# DCF77-Uhr-V4_1Big_OHW7.net
KiCad netlist of a schematic drawn in EAGLE
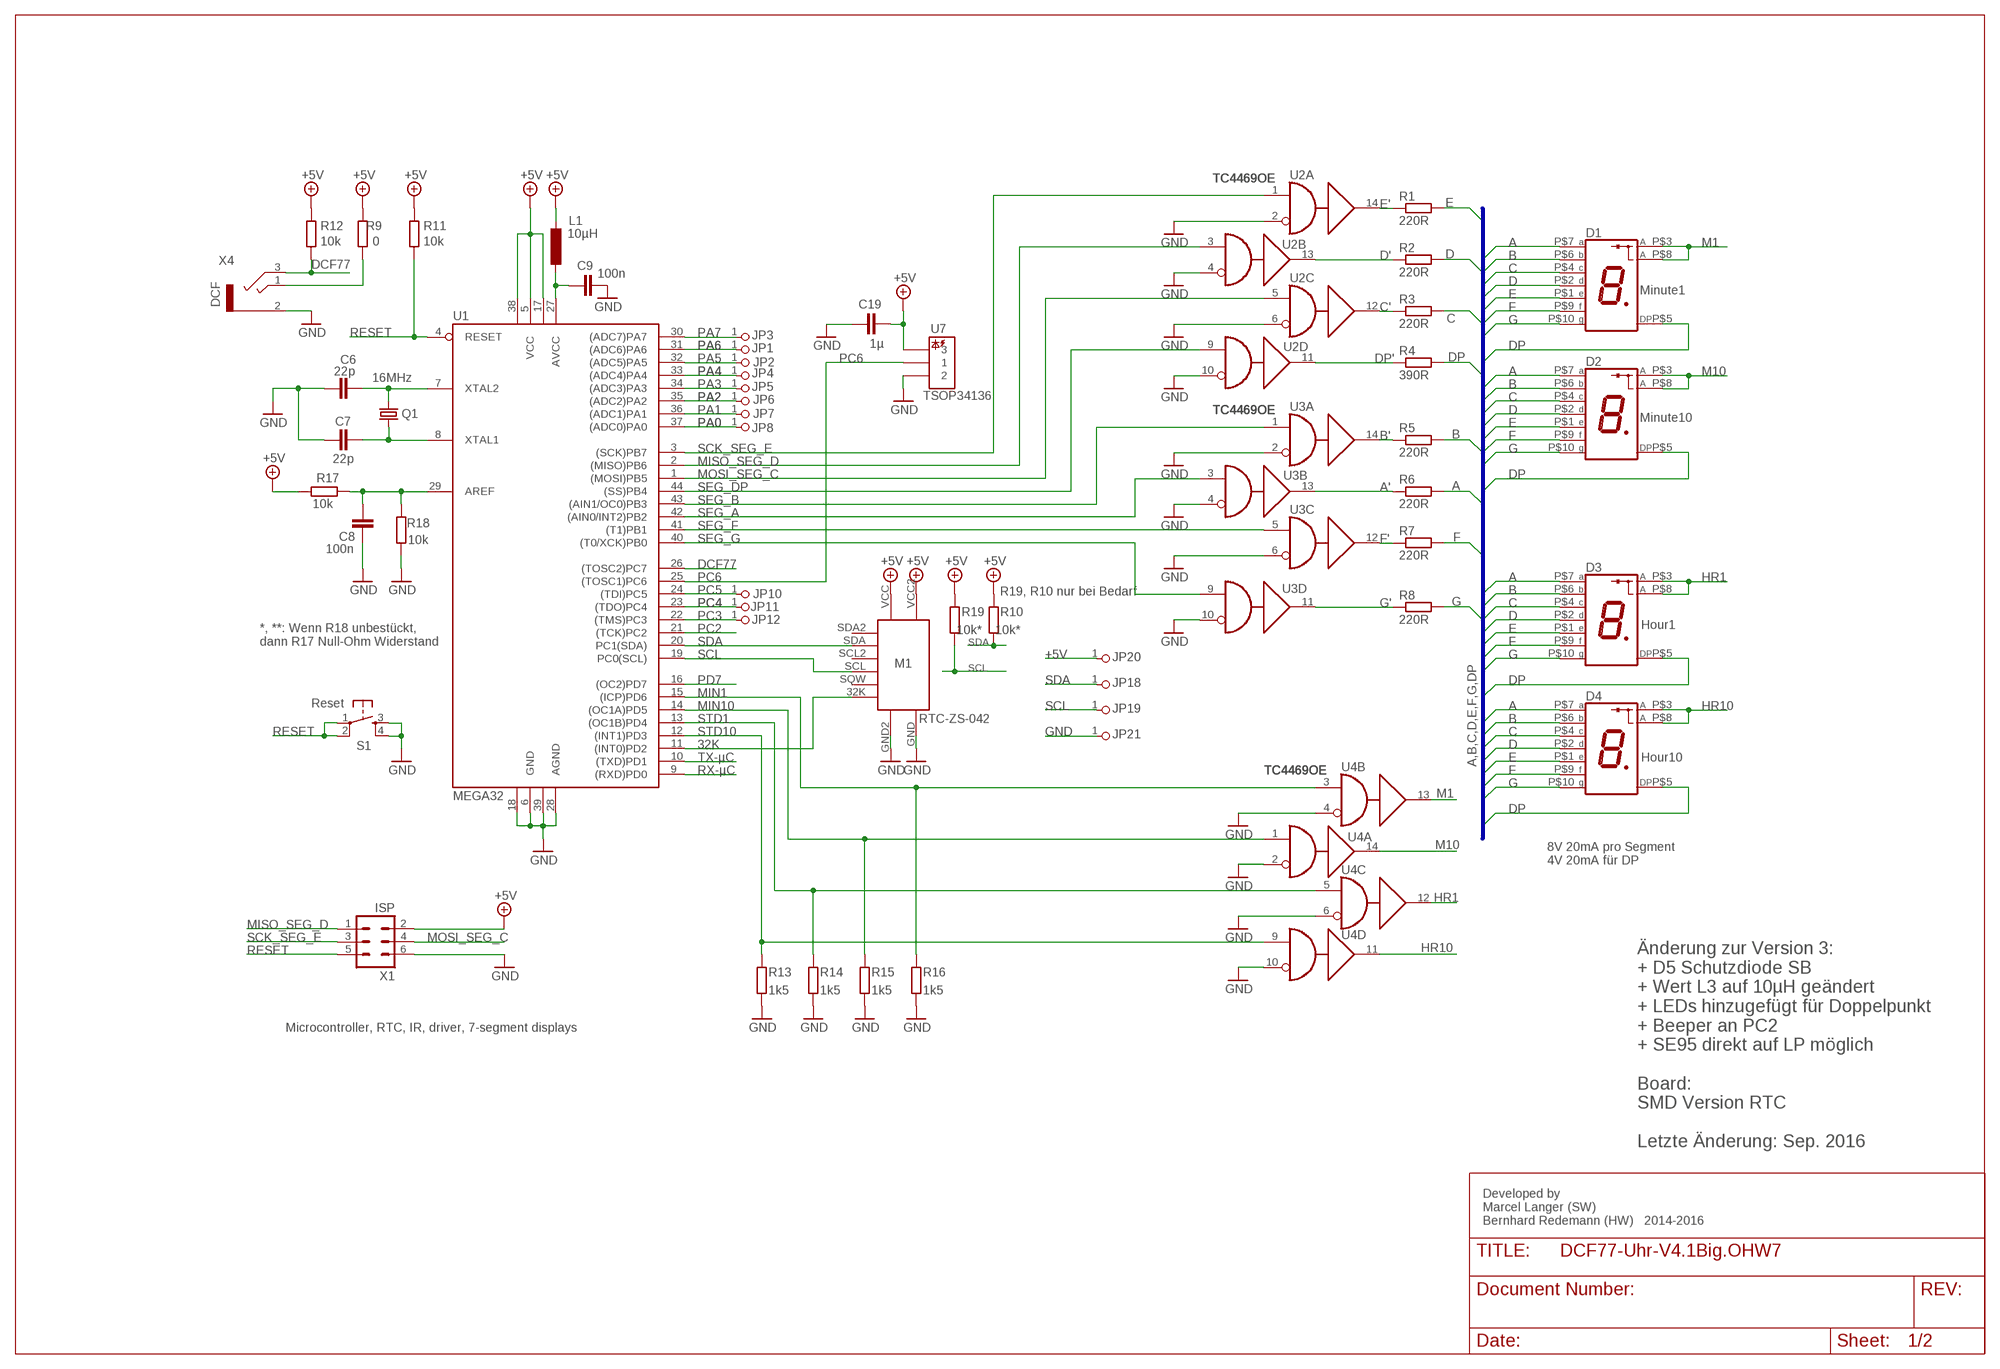
[diagram p0: schematic, sheet 1]
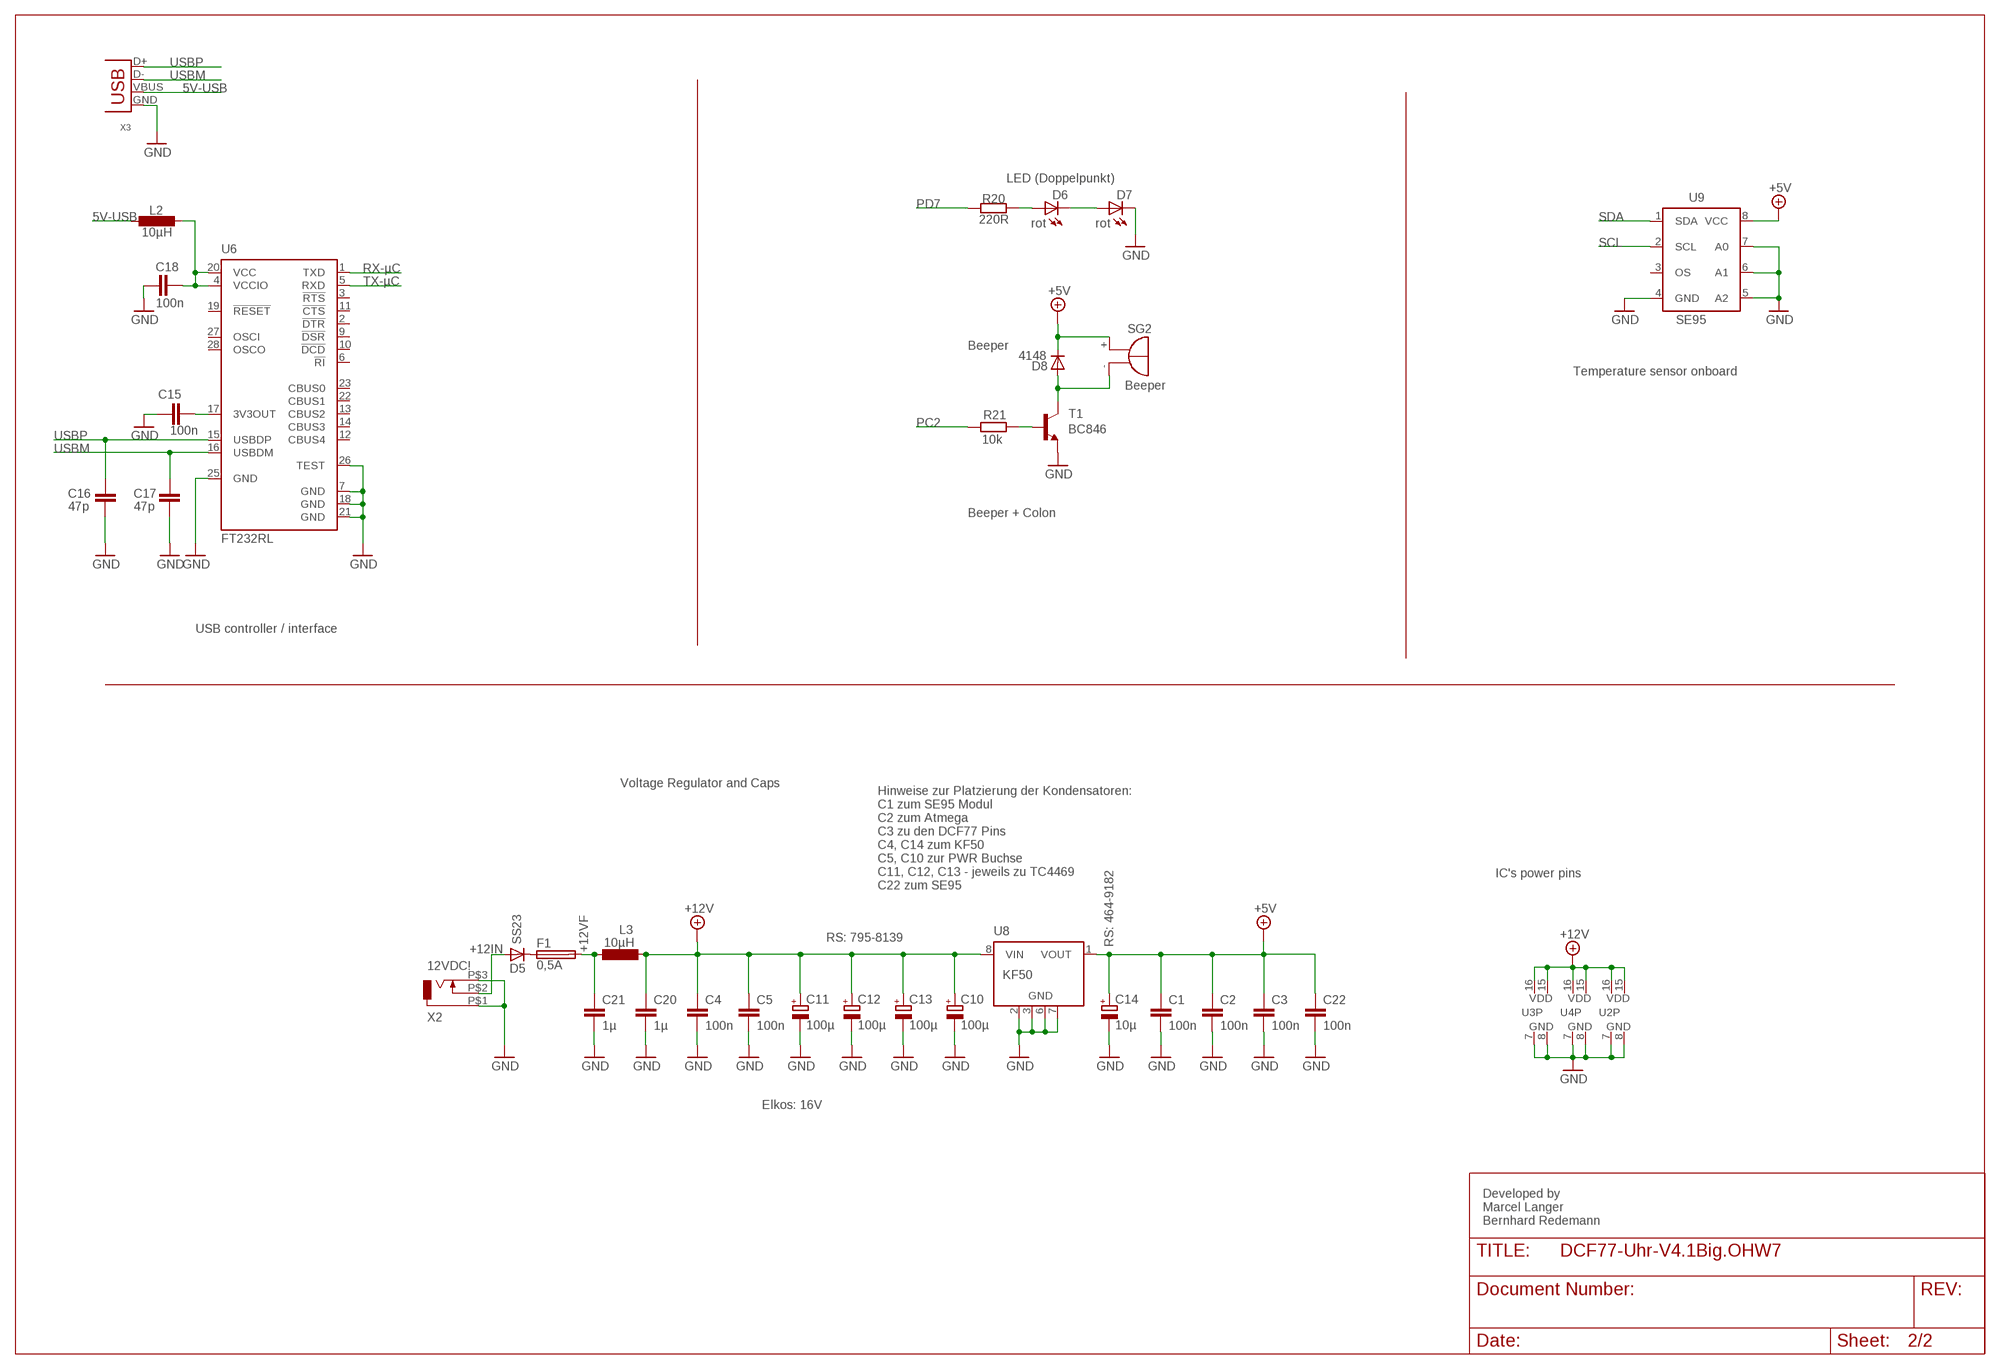
[diagram p1: schematic, sheet 2]

(export (version "E")
  (design (tool "Eeschema 10.0.6"))
  (components
    (comp (ref "C6")
      (value "22p")
      (footprint "eagle-import:C0805")
      (libsource (lib "eagle-import") (part "C-EUC0805"))
    )
    (comp (ref "C7")
      (value "22p")
      (footprint "eagle-import:C0805")
      (libsource (lib "eagle-import") (part "C-EUC0805"))
    )
    (comp (ref "C8")
      (value "100n")
      (footprint "eagle-import:C0805")
      (libsource (lib "eagle-import") (part "C-EUC0805"))
    )
    (comp (ref "C9")
      (value "100n")
      (footprint "eagle-import:C0805")
      (libsource (lib "eagle-import") (part "C-EUC0805"))
    )
    (comp (ref "C19")
      (value "1µ")
      (footprint "eagle-import:C0805")
      (libsource (lib "eagle-import") (part "C-EUC0805"))
    )
    (comp (ref "D1")
      (value "Minute1")
      (footprint "eagle-import:SA40-19EWA")
      (libsource (lib "eagle-import") (part "SA40-19EWA"))
    )
    (comp (ref "D2")
      (value "Minute10")
      (footprint "eagle-import:SA40-19EWA")
      (libsource (lib "eagle-import") (part "SA40-19EWA"))
    )
    (comp (ref "D3")
      (value "Hour1")
      (footprint "eagle-import:SA40-19EWA")
      (libsource (lib "eagle-import") (part "SA40-19EWA"))
    )
    (comp (ref "D4")
      (value "Hour10")
      (footprint "eagle-import:SA40-19EWA")
      (libsource (lib "eagle-import") (part "SA40-19EWA"))
    )
    (comp (ref "JP1")
      (value "PA6")
      (footprint "eagle-import:1X01")
      (libsource (lib "eagle-import") (part "PINHD-1X1"))
    )
    (comp (ref "JP2")
      (value "PC5")
      (footprint "eagle-import:1X01")
      (libsource (lib "eagle-import") (part "PINHD-1X1"))
    )
    (comp (ref "JP3")
      (value "PA6")
      (footprint "eagle-import:1X01")
      (libsource (lib "eagle-import") (part "PINHD-1X1"))
    )
    (comp (ref "JP4")
      (value "PA4")
      (footprint "eagle-import:1X01")
      (libsource (lib "eagle-import") (part "PINHD-1X1"))
    )
    (comp (ref "JP5")
      (value "PA3")
      (footprint "eagle-import:1X01")
      (libsource (lib "eagle-import") (part "PINHD-1X1"))
    )
    (comp (ref "JP6")
      (value "PA2")
      (footprint "eagle-import:1X01")
      (libsource (lib "eagle-import") (part "PINHD-1X1"))
    )
    (comp (ref "JP7")
      (value "PA1")
      (footprint "eagle-import:1X01")
      (libsource (lib "eagle-import") (part "PINHD-1X1"))
    )
    (comp (ref "JP8")
      (value "PA0")
      (footprint "eagle-import:1X01")
      (libsource (lib "eagle-import") (part "PINHD-1X1"))
    )
    (comp (ref "JP10")
      (value "PC5")
      (footprint "eagle-import:1X01")
      (libsource (lib "eagle-import") (part "PINHD-1X1"))
    )
    (comp (ref "JP11")
      (value "PC4")
      (footprint "eagle-import:1X01")
      (libsource (lib "eagle-import") (part "PINHD-1X1"))
    )
    (comp (ref "JP12")
      (value "PC3")
      (footprint "eagle-import:1X01")
      (libsource (lib "eagle-import") (part "PINHD-1X1"))
    )
    (comp (ref "JP18")
      (value "SDA")
      (footprint "eagle-import:1X01")
      (libsource (lib "eagle-import") (part "PINHD-1X1"))
    )
    (comp (ref "JP19")
      (value "SCL")
      (footprint "eagle-import:1X01")
      (libsource (lib "eagle-import") (part "PINHD-1X1"))
    )
    (comp (ref "JP20")
      (value "+5V")
      (footprint "eagle-import:1X01")
      (libsource (lib "eagle-import") (part "PINHD-1X1"))
    )
    (comp (ref "JP21")
      (value "GND")
      (footprint "eagle-import:1X01")
      (libsource (lib "eagle-import") (part "PINHD-1X1"))
    )
    (comp (ref "L1")
      (value "10µH")
      (footprint "eagle-import:L2825P")
      (libsource (lib "eagle-import") (part "L-EUL2825P"))
    )
    (comp (ref "M1")
      (value "RTC-ZS-042")
      (footprint "eagle-import:ZS-042-SMD")
      (libsource (lib "eagle-import") (part "RTC-ZS-042SMD"))
    )
    (comp (ref "Q1")
      (value "16MHz")
      (footprint "eagle-import:HC49UP")
      (libsource (lib "eagle-import") (part "CRYSTALHC49UP"))
    )
    (comp (ref "R1")
      (value "220R")
      (footprint "eagle-import:M0805")
      (libsource (lib "eagle-import") (part "R-EU_M0805"))
    )
    (comp (ref "R2")
      (value "220R")
      (footprint "eagle-import:M0805")
      (libsource (lib "eagle-import") (part "R-EU_M0805"))
    )
    (comp (ref "R3")
      (value "220R")
      (footprint "eagle-import:M0805")
      (libsource (lib "eagle-import") (part "R-EU_M0805"))
    )
    (comp (ref "R4")
      (value "390R")
      (footprint "eagle-import:M0805")
      (libsource (lib "eagle-import") (part "R-EU_M0805"))
    )
    (comp (ref "R5")
      (value "220R")
      (footprint "eagle-import:M0805")
      (libsource (lib "eagle-import") (part "R-EU_M0805"))
    )
    (comp (ref "R6")
      (value "220R")
      (footprint "eagle-import:M0805")
      (libsource (lib "eagle-import") (part "R-EU_M0805"))
    )
    (comp (ref "R7")
      (value "220R")
      (footprint "eagle-import:M0805")
      (libsource (lib "eagle-import") (part "R-EU_M0805"))
    )
    (comp (ref "R8")
      (value "220R")
      (footprint "eagle-import:M0805")
      (libsource (lib "eagle-import") (part "R-EU_M0805"))
    )
    (comp (ref "R9")
      (value "0")
      (footprint "eagle-import:M0805")
      (libsource (lib "eagle-import") (part "R-EU_M0805"))
    )
    (comp (ref "R10")
      (value "10k*")
      (footprint "eagle-import:M0805")
      (libsource (lib "eagle-import") (part "R-EU_M0805"))
    )
    (comp (ref "R11")
      (value "10k")
      (footprint "eagle-import:M0805")
      (libsource (lib "eagle-import") (part "R-EU_M0805"))
    )
    (comp (ref "R12")
      (value "10k")
      (footprint "eagle-import:M0805")
      (libsource (lib "eagle-import") (part "R-EU_M0805"))
    )
    (comp (ref "R13")
      (value "1k5")
      (footprint "eagle-import:M0805")
      (libsource (lib "eagle-import") (part "R-EU_M0805"))
    )
    (comp (ref "R14")
      (value "1k5")
      (footprint "eagle-import:M0805")
      (libsource (lib "eagle-import") (part "R-EU_M0805"))
    )
    (comp (ref "R15")
      (value "1k5")
      (footprint "eagle-import:M0805")
      (libsource (lib "eagle-import") (part "R-EU_M0805"))
    )
    (comp (ref "R16")
      (value "1k5")
      (footprint "eagle-import:M0805")
      (libsource (lib "eagle-import") (part "R-EU_M0805"))
    )
    (comp (ref "R17")
      (value "10k")
      (footprint "eagle-import:M0805")
      (libsource (lib "eagle-import") (part "R-EU_M0805"))
    )
    (comp (ref "R18")
      (value "10k")
      (footprint "eagle-import:M0805")
      (libsource (lib "eagle-import") (part "R-EU_M0805"))
    )
    (comp (ref "R19")
      (value "10k*")
      (footprint "eagle-import:M0805")
      (libsource (lib "eagle-import") (part "R-EU_M0805"))
    )
    (comp (ref "S1")
      (value "Reset")
      (footprint "eagle-import:DTSM-6")
      (libsource (lib "eagle-import") (part "DTSM-6"))
    )
    (comp (ref "U1")
      (value "MEGA32")
      (footprint "eagle-import:TQFP44")
      (libsource (lib "eagle-import") (part "MEGA32-A"))
    )
    (comp (ref "U2")
      (value "TC4469OE")
      (footprint "eagle-import:SO-16DW")
      (fields (field (name "MF") "MICROCHIP") (field (name "MPN") "TC4469COE"))
      (libsource (lib "eagle-import") (part "TC4469OE"))
    )
    (comp (ref "U3")
      (value "TC4469OE")
      (footprint "eagle-import:SO-16DW")
      (fields (field (name "MF") "MICROCHIP") (field (name "MPN") "TC4469COE"))
      (libsource (lib "eagle-import") (part "TC4469OE"))
    )
    (comp (ref "U4")
      (value "TC4469OE")
      (footprint "eagle-import:SO-16DW")
      (fields (field (name "MF") "MICROCHIP") (field (name "MPN") "TC4469COE"))
      (libsource (lib "eagle-import") (part "TC4469OE"))
    )
    (comp (ref "U7")
      (value "TSOP34136")
      (footprint "eagle-import:TSOP348")
      (libsource (lib "eagle-import") (part "TSOP34136"))
    )
    (comp (ref "X1")
      (value "ISP")
      (footprint "eagle-import:ML6")
      (libsource (lib "eagle-import") (part "ML6"))
    )
    (comp (ref "X4")
      (value "DCF")
      (footprint "eagle-import:1502_01")
      (libsource (lib "eagle-import") (part "1502_01"))
    )
    (comp (ref "C1")
      (value "100n")
      (footprint "eagle-import:C0805")
      (libsource (lib "eagle-import") (part "C-EUC0805"))
    )
    (comp (ref "C2")
      (value "100n")
      (footprint "eagle-import:C0805")
      (libsource (lib "eagle-import") (part "C-EUC0805"))
    )
    (comp (ref "C3")
      (value "100n")
      (footprint "eagle-import:C0805")
      (libsource (lib "eagle-import") (part "C-EUC0805"))
    )
    (comp (ref "C4")
      (value "100n")
      (footprint "eagle-import:C0805")
      (libsource (lib "eagle-import") (part "C-EUC0805"))
    )
    (comp (ref "C5")
      (value "100n")
      (footprint "eagle-import:C0805")
      (libsource (lib "eagle-import") (part "C-EUC0805"))
    )
    (comp (ref "C10")
      (value "100µ")
      (footprint "eagle-import:PANASONIC_D")
      (libsource (lib "eagle-import") (part "CPOL-EUD"))
    )
    (comp (ref "C11")
      (value "100µ")
      (footprint "eagle-import:PANASONIC_D")
      (libsource (lib "eagle-import") (part "CPOL-EUD"))
    )
    (comp (ref "C12")
      (value "100µ")
      (footprint "eagle-import:PANASONIC_D")
      (libsource (lib "eagle-import") (part "CPOL-EUD"))
    )
    (comp (ref "C13")
      (value "100µ")
      (footprint "eagle-import:PANASONIC_D")
      (libsource (lib "eagle-import") (part "CPOL-EUD"))
    )
    (comp (ref "C14")
      (value "10µ")
      (footprint "eagle-import:PANASONIC_B")
      (libsource (lib "eagle-import") (part "CPOL-EUB"))
    )
    (comp (ref "C15")
      (value "100n")
      (footprint "eagle-import:C0805")
      (libsource (lib "eagle-import") (part "C-EUC0805"))
    )
    (comp (ref "C16")
      (value "47p")
      (footprint "eagle-import:C0805")
      (libsource (lib "eagle-import") (part "C-EUC0805"))
    )
    (comp (ref "C17")
      (value "47p")
      (footprint "eagle-import:C0805")
      (libsource (lib "eagle-import") (part "C-EUC0805"))
    )
    (comp (ref "C18")
      (value "100n")
      (footprint "eagle-import:C0805")
      (libsource (lib "eagle-import") (part "C-EUC0805"))
    )
    (comp (ref "C20")
      (value "1µ")
      (footprint "eagle-import:C0805")
      (libsource (lib "eagle-import") (part "C-EUC0805"))
    )
    (comp (ref "C21")
      (value "1µ")
      (footprint "eagle-import:C0805")
      (libsource (lib "eagle-import") (part "C-EUC0805"))
    )
    (comp (ref "C22")
      (value "100n")
      (footprint "eagle-import:C0805")
      (libsource (lib "eagle-import") (part "C-EUC0805"))
    )
    (comp (ref "D5")
      (value "SS23")
      (footprint "eagle-import:SMB")
      (libsource (lib "eagle-import") (part "DIODE-SMB"))
    )
    (comp (ref "D6")
      (value "rot")
      (footprint "eagle-import:LED10MM")
      (libsource (lib "eagle-import") (part "LED10MM"))
    )
    (comp (ref "D7")
      (value "rot")
      (footprint "eagle-import:LED10MM")
      (libsource (lib "eagle-import") (part "LED10MM"))
    )
    (comp (ref "D8")
      (value "4148")
      (footprint "eagle-import:DO214BA")
      (libsource (lib "eagle-import") (part "DIODE-DO214BA"))
    )
    (comp (ref "F1")
      (value "0,5A")
      (footprint "eagle-import:19560")
      (fields (field (name "MPN") "56000001009"))
      (libsource (lib "eagle-import") (part "19560"))
    )
    (comp (ref "L2")
      (value "10µH")
      (footprint "eagle-import:L2825P")
      (libsource (lib "eagle-import") (part "L-EUL2825P"))
    )
    (comp (ref "L3")
      (value "10µH")
      (footprint "eagle-import:L2825P")
      (libsource (lib "eagle-import") (part "L-EUL2825P"))
    )
    (comp (ref "R20")
      (value "220R")
      (footprint "eagle-import:M0805")
      (libsource (lib "eagle-import") (part "R-EU_M0805"))
    )
    (comp (ref "R21")
      (value "10k")
      (footprint "eagle-import:M0805")
      (libsource (lib "eagle-import") (part "R-EU_M0805"))
    )
    (comp (ref "SG2")
      (value "Beeper")
      (footprint "eagle-import:BMT1205XH7.5")
      (libsource (lib "eagle-import") (part "BMT1205XH7.5"))
    )
    (comp (ref "T1")
      (value "BC846")
      (footprint "eagle-import:SOT23")
      (libsource (lib "eagle-import") (part "BC846"))
    )
    (comp (ref "U6")
      (value "FT232RL")
      (footprint "eagle-import:SSOP28")
      (libsource (lib "eagle-import") (part "FT232RL"))
    )
    (comp (ref "U8")
      (value "KF50")
      (footprint "eagle-import:SO08")
      (libsource (lib "eagle-import") (part "78LSMD05"))
    )
    (comp (ref "U9")
      (value "SE95")
      (footprint "eagle-import:SO08")
      (libsource (lib "eagle-import") (part "LM75SMD"))
    )
    (comp (ref "X2")
      (value "12VDC!")
      (footprint "eagle-import:DCJ04-021")
      (libsource (lib "eagle-import") (part "DCJ0202DCJ04-021"))
    )
    (comp (ref "X3")
      (value "USB")
      (footprint "eagle-import:USB-B180")
      (libsource (lib "eagle-import") (part "USB-B180"))
    )
  )
  (nets
    (net (code "1") (name "+5V") (class "Default")
      (node (ref "C1") (pin "1") (pinfunction "1_1") (pintype "passive"))
      (node (ref "C14") (pin "+") (pinfunction "+_+") (pintype "passive"))
      (node (ref "C19") (pin "2") (pinfunction "2_2") (pintype "passive"))
      (node (ref "C2") (pin "1") (pinfunction "1_1") (pintype "passive"))
      (node (ref "C22") (pin "1") (pinfunction "1_1") (pintype "passive"))
      (node (ref "C3") (pin "1") (pinfunction "1_1") (pintype "passive"))
      (node (ref "D8") (pin "C") (pinfunction "C_C") (pintype "passive"))
      (node (ref "JP20") (pin "1") (pinfunction "1_1") (pintype "passive"))
      (node (ref "L1") (pin "2") (pinfunction "2_2") (pintype "passive"))
      (node (ref "M1") (pin "VCC") (pinfunction "P$9_VCC") (pintype "bidirectional"))
      (node (ref "M1") (pin "VCC2") (pinfunction "P$10_VCC2") (pintype "bidirectional"))
      (node (ref "R10") (pin "2") (pinfunction "2_2") (pintype "passive"))
      (node (ref "R11") (pin "2") (pinfunction "2_2") (pintype "passive"))
      (node (ref "R12") (pin "2") (pinfunction "2_2") (pintype "passive"))
      (node (ref "R17") (pin "1") (pinfunction "1_1") (pintype "passive"))
      (node (ref "R19") (pin "2") (pinfunction "2_2") (pintype "passive"))
      (node (ref "R9") (pin "2") (pinfunction "2_2") (pintype "passive"))
      (node (ref "SG2") (pin "+") (pinfunction "+_+") (pintype "passive"))
      (node (ref "U1") (pin "17") (pinfunction "VCC1_17") (pintype "power_in"))
      (node (ref "U1") (pin "38") (pinfunction "VCC2_38") (pintype "power_in"))
      (node (ref "U1") (pin "5") (pinfunction "VCC_5") (pintype "power_in"))
      (node (ref "U7") (pin "3") (pinfunction "3_3") (pintype "power_in"))
      (node (ref "U8") (pin "1") (pinfunction "VOUT_1") (pintype "bidirectional"))
      (node (ref "U9") (pin "8") (pinfunction "VCC_8") (pintype "power_in"))
      (node (ref "X1") (pin "2") (pinfunction "2_2") (pintype "passive"))
    )
    (net (code "2") (name "+12IN") (class "Default")
      (node (ref "D5") (pin "A") (pinfunction "A_A") (pintype "passive"))
      (node (ref "X2") (pin "P$2") (pinfunction "2_P$2") (pintype "passive"))
    )
    (net (code "3") (name "+12V") (class "Default")
      (node (ref "C10") (pin "+") (pinfunction "+_+") (pintype "passive"))
      (node (ref "C11") (pin "+") (pinfunction "+_+") (pintype "passive"))
      (node (ref "C12") (pin "+") (pinfunction "+_+") (pintype "passive"))
      (node (ref "C13") (pin "+") (pinfunction "+_+") (pintype "passive"))
      (node (ref "C20") (pin "1") (pinfunction "1_1") (pintype "passive"))
      (node (ref "C4") (pin "1") (pinfunction "1_1") (pintype "passive"))
      (node (ref "C5") (pin "1") (pinfunction "1_1") (pintype "passive"))
      (node (ref "L3") (pin "1") (pinfunction "1_1") (pintype "passive"))
      (node (ref "U2") (pin "15") (pinfunction "VDD_15") (pintype "power_in"))
      (node (ref "U2") (pin "16") (pinfunction "VDD_16") (pintype "power_in"))
      (node (ref "U3") (pin "15") (pinfunction "VDD_15") (pintype "power_in"))
      (node (ref "U3") (pin "16") (pinfunction "VDD_16") (pintype "power_in"))
      (node (ref "U4") (pin "15") (pinfunction "VDD_15") (pintype "power_in"))
      (node (ref "U4") (pin "16") (pinfunction "VDD_16") (pintype "power_in"))
      (node (ref "U8") (pin "8") (pinfunction "VIN_8") (pintype "passive"))
    )
    (net (code "4") (name "+12VF") (class "Default")
      (node (ref "C21") (pin "1") (pinfunction "1_1") (pintype "passive"))
      (node (ref "F1") (pin "2") (pinfunction "2_2") (pintype "passive"))
      (node (ref "L3") (pin "2") (pinfunction "2_2") (pintype "passive"))
    )
    (net (code "6") (name "5V-USB") (class "Default")
      (node (ref "L2") (pin "2") (pinfunction "2_2") (pintype "passive"))
      (node (ref "X3") (pin "VBUS") (pinfunction "VBUS_VBUS") (pintype "bidirectional"))
    )
    (net (code "7") (name "32K") (class "Default")
      (node (ref "M1") (pin "32K") (pinfunction "P$1_32K") (pintype "bidirectional"))
      (node (ref "U1") (pin "11") (pinfunction "(INT0)PD2_11") (pintype "bidirectional"))
    )
    (net (code "8") (name "A") (class "Default")
      (node (ref "D1") (pin "P$7") (pinfunction "A_P$7") (pintype "passive"))
      (node (ref "D2") (pin "P$7") (pinfunction "A_P$7") (pintype "passive"))
      (node (ref "D3") (pin "P$7") (pinfunction "A_P$7") (pintype "passive"))
      (node (ref "D4") (pin "P$7") (pinfunction "A_P$7") (pintype "passive"))
      (node (ref "R6") (pin "2") (pinfunction "2_2") (pintype "passive"))
    )
    (net (code "9") (name "A'") (class "Default")
      (node (ref "R6") (pin "1") (pinfunction "1_1") (pintype "passive"))
      (node (ref "U3") (pin "13") (pinfunction "Y_13") (pintype "output"))
    )
    (net (code "10") (name "B") (class "Default")
      (node (ref "D1") (pin "P$6") (pinfunction "B_P$6") (pintype "passive"))
      (node (ref "D2") (pin "P$6") (pinfunction "B_P$6") (pintype "passive"))
      (node (ref "D3") (pin "P$6") (pinfunction "B_P$6") (pintype "passive"))
      (node (ref "D4") (pin "P$6") (pinfunction "B_P$6") (pintype "passive"))
      (node (ref "R5") (pin "2") (pinfunction "2_2") (pintype "passive"))
    )
    (net (code "11") (name "B'") (class "Default")
      (node (ref "R5") (pin "1") (pinfunction "1_1") (pintype "passive"))
      (node (ref "U3") (pin "14") (pinfunction "Y_14") (pintype "output"))
    )
    (net (code "12") (name "C") (class "Default")
      (node (ref "D1") (pin "P$4") (pinfunction "C_P$4") (pintype "passive"))
      (node (ref "D2") (pin "P$4") (pinfunction "C_P$4") (pintype "passive"))
      (node (ref "D3") (pin "P$4") (pinfunction "C_P$4") (pintype "passive"))
      (node (ref "D4") (pin "P$4") (pinfunction "C_P$4") (pintype "passive"))
      (node (ref "R3") (pin "2") (pinfunction "2_2") (pintype "passive"))
    )
    (net (code "13") (name "C'") (class "Default")
      (node (ref "R3") (pin "1") (pinfunction "1_1") (pintype "passive"))
      (node (ref "U2") (pin "12") (pinfunction "Y_12") (pintype "output"))
    )
    (net (code "14") (name "D") (class "Default")
      (node (ref "D1") (pin "P$2") (pinfunction "D_P$2") (pintype "passive"))
      (node (ref "D2") (pin "P$2") (pinfunction "D_P$2") (pintype "passive"))
      (node (ref "D3") (pin "P$2") (pinfunction "D_P$2") (pintype "passive"))
      (node (ref "D4") (pin "P$2") (pinfunction "D_P$2") (pintype "passive"))
      (node (ref "R2") (pin "2") (pinfunction "2_2") (pintype "passive"))
    )
    (net (code "15") (name "D'") (class "Default")
      (node (ref "R2") (pin "1") (pinfunction "1_1") (pintype "passive"))
      (node (ref "U2") (pin "13") (pinfunction "Y_13") (pintype "output"))
    )
    (net (code "16") (name "DCF77") (class "Default")
      (node (ref "R12") (pin "1") (pinfunction "1_1") (pintype "passive"))
      (node (ref "U1") (pin "26") (pinfunction "(TOSC2)PC7_26") (pintype "bidirectional"))
      (node (ref "X4") (pin "3") (pinfunction "2_3") (pintype "passive"))
    )
    (net (code "17") (name "DP") (class "Default")
      (node (ref "D1") (pin "P$5") (pinfunction "DP_P$5") (pintype "passive"))
      (node (ref "D2") (pin "P$5") (pinfunction "DP_P$5") (pintype "passive"))
      (node (ref "D3") (pin "P$5") (pinfunction "DP_P$5") (pintype "passive"))
      (node (ref "D4") (pin "P$5") (pinfunction "DP_P$5") (pintype "passive"))
      (node (ref "R4") (pin "2") (pinfunction "2_2") (pintype "passive"))
    )
    (net (code "18") (name "DP'") (class "Default")
      (node (ref "R4") (pin "1") (pinfunction "1_1") (pintype "passive"))
      (node (ref "U2") (pin "11") (pinfunction "Y_11") (pintype "output"))
    )
    (net (code "19") (name "E") (class "Default")
      (node (ref "D1") (pin "P$1") (pinfunction "E_P$1") (pintype "passive"))
      (node (ref "D2") (pin "P$1") (pinfunction "E_P$1") (pintype "passive"))
      (node (ref "D3") (pin "P$1") (pinfunction "E_P$1") (pintype "passive"))
      (node (ref "D4") (pin "P$1") (pinfunction "E_P$1") (pintype "passive"))
      (node (ref "R1") (pin "2") (pinfunction "2_2") (pintype "passive"))
    )
    (net (code "20") (name "E'") (class "Default")
      (node (ref "R1") (pin "1") (pinfunction "1_1") (pintype "passive"))
      (node (ref "U2") (pin "14") (pinfunction "Y_14") (pintype "output"))
    )
    (net (code "21") (name "F") (class "Default")
      (node (ref "D1") (pin "P$9") (pinfunction "F_P$9") (pintype "passive"))
      (node (ref "D2") (pin "P$9") (pinfunction "F_P$9") (pintype "passive"))
      (node (ref "D3") (pin "P$9") (pinfunction "F_P$9") (pintype "passive"))
      (node (ref "D4") (pin "P$9") (pinfunction "F_P$9") (pintype "passive"))
      (node (ref "R7") (pin "2") (pinfunction "2_2") (pintype "passive"))
    )
    (net (code "22") (name "F'") (class "Default")
      (node (ref "R7") (pin "1") (pinfunction "1_1") (pintype "passive"))
      (node (ref "U3") (pin "12") (pinfunction "Y_12") (pintype "output"))
    )
    (net (code "23") (name "G") (class "Default")
      (node (ref "D1") (pin "P$10") (pinfunction "G_P$10") (pintype "passive"))
      (node (ref "D2") (pin "P$10") (pinfunction "G_P$10") (pintype "passive"))
      (node (ref "D3") (pin "P$10") (pinfunction "G_P$10") (pintype "passive"))
      (node (ref "D4") (pin "P$10") (pinfunction "G_P$10") (pintype "passive"))
      (node (ref "R8") (pin "2") (pinfunction "2_2") (pintype "passive"))
    )
    (net (code "24") (name "G'") (class "Default")
      (node (ref "R8") (pin "1") (pinfunction "1_1") (pintype "passive"))
      (node (ref "U3") (pin "11") (pinfunction "Y_11") (pintype "output"))
    )
    (net (code "25") (name "GND") (class "Default")
      (node (ref "C1") (pin "2") (pinfunction "2_2") (pintype "passive"))
      (node (ref "C10") (pin "-") (pinfunction "-_-") (pintype "passive"))
      (node (ref "C11") (pin "-") (pinfunction "-_-") (pintype "passive"))
      (node (ref "C12") (pin "-") (pinfunction "-_-") (pintype "passive"))
      (node (ref "C13") (pin "-") (pinfunction "-_-") (pintype "passive"))
      (node (ref "C14") (pin "-") (pinfunction "-_-") (pintype "passive"))
      (node (ref "C15") (pin "1") (pinfunction "1_1") (pintype "passive"))
      (node (ref "C16") (pin "1") (pinfunction "1_1") (pintype "passive"))
      (node (ref "C17") (pin "1") (pinfunction "1_1") (pintype "passive"))
      (node (ref "C18") (pin "1") (pinfunction "1_1") (pintype "passive"))
      (node (ref "C19") (pin "1") (pinfunction "1_1") (pintype "passive"))
      (node (ref "C2") (pin "2") (pinfunction "2_2") (pintype "passive"))
      (node (ref "C20") (pin "2") (pinfunction "2_2") (pintype "passive"))
      (node (ref "C21") (pin "2") (pinfunction "2_2") (pintype "passive"))
      (node (ref "C22") (pin "2") (pinfunction "2_2") (pintype "passive"))
      (node (ref "C3") (pin "2") (pinfunction "2_2") (pintype "passive"))
      (node (ref "C4") (pin "2") (pinfunction "2_2") (pintype "passive"))
      (node (ref "C5") (pin "2") (pinfunction "2_2") (pintype "passive"))
      (node (ref "C6") (pin "1") (pinfunction "1_1") (pintype "passive"))
      (node (ref "C7") (pin "1") (pinfunction "1_1") (pintype "passive"))
      (node (ref "C8") (pin "1") (pinfunction "1_1") (pintype "passive"))
      (node (ref "C9") (pin "2") (pinfunction "2_2") (pintype "passive"))
      (node (ref "D7") (pin "K") (pinfunction "C_K") (pintype "passive"))
      (node (ref "JP21") (pin "1") (pinfunction "1_1") (pintype "passive"))
      (node (ref "M1") (pin "GND") (pinfunction "P$7_GND") (pintype "bidirectional"))
      (node (ref "M1") (pin "GND2") (pinfunction "P$8_GND2") (pintype "bidirectional"))
      (node (ref "R13") (pin "1") (pinfunction "1_1") (pintype "passive"))
      (node (ref "R14") (pin "1") (pinfunction "1_1") (pintype "passive"))
      (node (ref "R15") (pin "1") (pinfunction "1_1") (pintype "passive"))
      (node (ref "R16") (pin "1") (pinfunction "1_1") (pintype "passive"))
      (node (ref "R18") (pin "1") (pinfunction "1_1") (pintype "passive"))
      (node (ref "S1") (pin "3") (pinfunction "3_3") (pintype "passive"))
      (node (ref "S1") (pin "4") (pinfunction "4_4") (pintype "passive"))
      (node (ref "T1") (pin "2") (pinfunction "E_2") (pintype "passive"))
      (node (ref "U1") (pin "18") (pinfunction "GND1_18") (pintype "power_in"))
      (node (ref "U1") (pin "28") (pinfunction "AGND_28") (pintype "power_in"))
      (node (ref "U1") (pin "39") (pinfunction "GND2_39") (pintype "power_in"))
      (node (ref "U1") (pin "6") (pinfunction "GND_6") (pintype "power_in"))
      (node (ref "U2") (pin "10") (pinfunction "B_10") (pintype "input"))
      (node (ref "U2") (pin "2") (pinfunction "B_2") (pintype "input"))
      (node (ref "U2") (pin "4") (pinfunction "B_4") (pintype "input"))
      (node (ref "U2") (pin "6") (pinfunction "B_6") (pintype "input"))
      (node (ref "U2") (pin "7") (pinfunction "GND_7") (pintype "power_in"))
      (node (ref "U2") (pin "8") (pinfunction "GND_8") (pintype "power_in"))
      (node (ref "U3") (pin "10") (pinfunction "B_10") (pintype "input"))
      (node (ref "U3") (pin "2") (pinfunction "B_2") (pintype "input"))
      (node (ref "U3") (pin "4") (pinfunction "B_4") (pintype "input"))
      (node (ref "U3") (pin "6") (pinfunction "B_6") (pintype "input"))
      (node (ref "U3") (pin "7") (pinfunction "GND_7") (pintype "power_in"))
      (node (ref "U3") (pin "8") (pinfunction "GND_8") (pintype "power_in"))
      (node (ref "U4") (pin "10") (pinfunction "B_10") (pintype "input"))
      (node (ref "U4") (pin "2") (pinfunction "B_2") (pintype "input"))
      (node (ref "U4") (pin "4") (pinfunction "B_4") (pintype "input"))
      (node (ref "U4") (pin "6") (pinfunction "B_6") (pintype "input"))
      (node (ref "U4") (pin "7") (pinfunction "GND_7") (pintype "power_in"))
      (node (ref "U4") (pin "8") (pinfunction "GND_8") (pintype "power_in"))
      (node (ref "U6") (pin "18") (pinfunction "GND_18") (pintype "power_in"))
      (node (ref "U6") (pin "21") (pinfunction "GND_21") (pintype "power_in"))
      (node (ref "U6") (pin "25") (pinfunction "GND_25") (pintype "power_in"))
      (node (ref "U6") (pin "26") (pinfunction "TEST_26") (pintype "input"))
      (node (ref "U6") (pin "7") (pinfunction "GND_7") (pintype "power_in"))
      (node (ref "U7") (pin "2") (pinfunction "2_2") (pintype "bidirectional"))
      (node (ref "U8") (pin "2") (pinfunction "GND_2") (pintype "power_in"))
      (node (ref "U8") (pin "3") (pinfunction "GND_3") (pintype "power_in"))
      (node (ref "U8") (pin "6") (pinfunction "GND_6") (pintype "power_in"))
      (node (ref "U8") (pin "7") (pinfunction "GND_7") (pintype "power_in"))
      (node (ref "U9") (pin "4") (pinfunction "GND_4") (pintype "power_in"))
      (node (ref "U9") (pin "5") (pinfunction "A2_5") (pintype "input"))
      (node (ref "U9") (pin "6") (pinfunction "A1_6") (pintype "input"))
      (node (ref "U9") (pin "7") (pinfunction "A0_7") (pintype "input"))
      (node (ref "X1") (pin "6") (pinfunction "6_6") (pintype "passive"))
      (node (ref "X2") (pin "P$1") (pinfunction "1_P$1") (pintype "passive"))
      (node (ref "X2") (pin "P$3") (pinfunction "3_P$3") (pintype "passive"))
      (node (ref "X3") (pin "GND") (pinfunction "GND_GND") (pintype "bidirectional"))
      (node (ref "X4") (pin "2") (pinfunction "1_2") (pintype "passive"))
    )
    (net (code "26") (name "HR1") (class "Default")
      (node (ref "D3") (pin "P$3") (pinfunction "A_P$3") (pintype "passive"))
      (node (ref "D3") (pin "P$8") (pinfunction "A_P$8") (pintype "passive"))
      (node (ref "U4") (pin "12") (pinfunction "Y_12") (pintype "output"))
    )
    (net (code "27") (name "HR10") (class "Default")
      (node (ref "D4") (pin "P$3") (pinfunction "A_P$3") (pintype "passive"))
      (node (ref "D4") (pin "P$8") (pinfunction "A_P$8") (pintype "passive"))
      (node (ref "U4") (pin "11") (pinfunction "Y_11") (pintype "output"))
    )
    (net (code "28") (name "M1") (class "Default")
      (node (ref "D1") (pin "P$3") (pinfunction "A_P$3") (pintype "passive"))
      (node (ref "D1") (pin "P$8") (pinfunction "A_P$8") (pintype "passive"))
      (node (ref "U4") (pin "13") (pinfunction "Y_13") (pintype "output"))
    )
    (net (code "29") (name "M10") (class "Default")
      (node (ref "D2") (pin "P$3") (pinfunction "A_P$3") (pintype "passive"))
      (node (ref "D2") (pin "P$8") (pinfunction "A_P$8") (pintype "passive"))
      (node (ref "U4") (pin "14") (pinfunction "Y_14") (pintype "output"))
    )
    (net (code "30") (name "MIN1") (class "Default")
      (node (ref "R16") (pin "2") (pinfunction "2_2") (pintype "passive"))
      (node (ref "U1") (pin "15") (pinfunction "(ICP)PD6_15") (pintype "bidirectional"))
      (node (ref "U4") (pin "3") (pinfunction "A_3") (pintype "input"))
    )
    (net (code "31") (name "MIN10") (class "Default")
      (node (ref "R15") (pin "2") (pinfunction "2_2") (pintype "passive"))
      (node (ref "U1") (pin "14") (pinfunction "(OC1A)PD5_14") (pintype "bidirectional"))
      (node (ref "U4") (pin "1") (pinfunction "A_1") (pintype "input"))
    )
    (net (code "32") (name "MISO_SEG_D") (class "Default")
      (node (ref "U1") (pin "2") (pinfunction "(MISO)PB6_2") (pintype "bidirectional"))
      (node (ref "U2") (pin "3") (pinfunction "A_3") (pintype "input"))
      (node (ref "X1") (pin "1") (pinfunction "1_1") (pintype "passive"))
    )
    (net (code "33") (name "MOSI_SEG_C") (class "Default")
      (node (ref "U1") (pin "1") (pinfunction "(MOSI)PB5_1") (pintype "bidirectional"))
      (node (ref "U2") (pin "5") (pinfunction "A_5") (pintype "input"))
      (node (ref "X1") (pin "4") (pinfunction "4_4") (pintype "passive"))
    )
    (net (code "34") (name "Net-(D5-PadC)") (class "Default")
      (node (ref "D5") (pin "C") (pinfunction "C_C") (pintype "passive"))
      (node (ref "F1") (pin "1") (pinfunction "1_1") (pintype "passive"))
    )
    (net (code "35") (name "Net-(D6-C)") (class "Default")
      (node (ref "D6") (pin "K") (pinfunction "C_K") (pintype "passive"))
      (node (ref "D7") (pin "A") (pinfunction "A_A") (pintype "passive"))
    )
    (net (code "36") (name "Net-(D6-PadA)") (class "Default")
      (node (ref "D6") (pin "A") (pinfunction "A_A") (pintype "passive"))
      (node (ref "R20") (pin "2") (pinfunction "2_2") (pintype "passive"))
    )
    (net (code "37") (name "Net-(T1-B)") (class "Default")
      (node (ref "R21") (pin "1") (pinfunction "1_1") (pintype "passive"))
      (node (ref "T1") (pin "1") (pinfunction "B_1") (pintype "passive"))
    )
    (net (code "38") (name "Net-(T1-C)") (class "Default")
      (node (ref "D8") (pin "A") (pinfunction "A_A") (pintype "passive"))
      (node (ref "SG2") (pin "-") (pinfunction "-_-") (pintype "passive"))
      (node (ref "T1") (pin "3") (pinfunction "C_3") (pintype "passive"))
    )
    (net (code "39") (name "Net-(U1-AREF)") (class "Default")
      (node (ref "C8") (pin "2") (pinfunction "2_2") (pintype "passive"))
      (node (ref "R17") (pin "2") (pinfunction "2_2") (pintype "passive"))
      (node (ref "R18") (pin "2") (pinfunction "2_2") (pintype "passive"))
      (node (ref "U1") (pin "29") (pinfunction "AREF_29") (pintype "power_in"))
    )
    (net (code "40") (name "Net-(U1-AVCC)") (class "Default")
      (node (ref "C9") (pin "1") (pinfunction "1_1") (pintype "passive"))
      (node (ref "L1") (pin "1") (pinfunction "1_1") (pintype "passive"))
      (node (ref "U1") (pin "27") (pinfunction "AVCC_27") (pintype "power_in"))
    )
    (net (code "41") (name "Net-(U1-XTAL1)") (class "Default")
      (node (ref "C7") (pin "2") (pinfunction "2_2") (pintype "passive"))
      (node (ref "Q1") (pin "1") (pinfunction "1_1") (pintype "passive"))
      (node (ref "U1") (pin "8") (pinfunction "XTAL1_8") (pintype "bidirectional"))
    )
    (net (code "42") (name "Net-(U1-XTAL2)") (class "Default")
      (node (ref "C6") (pin "2") (pinfunction "2_2") (pintype "passive"))
      (node (ref "Q1") (pin "2") (pinfunction "2_2") (pintype "passive"))
      (node (ref "U1") (pin "7") (pinfunction "XTAL2_7") (pintype "bidirectional"))
    )
    (net (code "43") (name "Net-(U6-3V3OUT)") (class "Default")
      (node (ref "C15") (pin "2") (pinfunction "2_2") (pintype "passive"))
      (node (ref "U6") (pin "17") (pinfunction "3V3OUT_17") (pintype "output"))
    )
    (net (code "44") (name "Net-(U6-VCC)") (class "Default")
      (node (ref "C18") (pin "2") (pinfunction "2_2") (pintype "passive"))
      (node (ref "L2") (pin "1") (pinfunction "1_1") (pintype "passive"))
      (node (ref "U6") (pin "20") (pinfunction "VCC_20") (pintype "power_in"))
      (node (ref "U6") (pin "4") (pinfunction "VCCIO_4") (pintype "power_in"))
    )
    (net (code "45") (name "Net-(X4-3)") (class "Default")
      (node (ref "R9") (pin "1") (pinfunction "1_1") (pintype "passive"))
      (node (ref "X4") (pin "1") (pinfunction "3_1") (pintype "passive"))
    )
    (net (code "46") (name "PA0") (class "Default")
      (node (ref "JP8") (pin "1") (pinfunction "1_1") (pintype "passive"))
      (node (ref "U1") (pin "37") (pinfunction "(ADC0)PA0_37") (pintype "bidirectional"))
    )
    (net (code "47") (name "PA1") (class "Default")
      (node (ref "JP7") (pin "1") (pinfunction "1_1") (pintype "passive"))
      (node (ref "U1") (pin "36") (pinfunction "(ADC1)PA1_36") (pintype "bidirectional"))
    )
    (net (code "48") (name "PA2") (class "Default")
      (node (ref "JP6") (pin "1") (pinfunction "1_1") (pintype "passive"))
      (node (ref "U1") (pin "35") (pinfunction "(ADC2)PA2_35") (pintype "bidirectional"))
    )
    (net (code "49") (name "PA3") (class "Default")
      (node (ref "JP5") (pin "1") (pinfunction "1_1") (pintype "passive"))
      (node (ref "U1") (pin "34") (pinfunction "(ADC3)PA3_34") (pintype "bidirectional"))
    )
    (net (code "50") (name "PA4") (class "Default")
      (node (ref "JP4") (pin "1") (pinfunction "1_1") (pintype "passive"))
      (node (ref "U1") (pin "33") (pinfunction "(ADC4)PA4_33") (pintype "bidirectional"))
    )
    (net (code "51") (name "PA5") (class "Default")
      (node (ref "JP2") (pin "1") (pinfunction "1_1") (pintype "passive"))
      (node (ref "U1") (pin "32") (pinfunction "(ADC5)PA5_32") (pintype "bidirectional"))
    )
    (net (code "52") (name "PA6") (class "Default")
      (node (ref "JP1") (pin "1") (pinfunction "1_1") (pintype "passive"))
      (node (ref "U1") (pin "31") (pinfunction "(ADC6)PA6_31") (pintype "bidirectional"))
    )
    (net (code "53") (name "PA7") (class "Default")
      (node (ref "JP3") (pin "1") (pinfunction "1_1") (pintype "passive"))
      (node (ref "U1") (pin "30") (pinfunction "(ADC7)PA7_30") (pintype "bidirectional"))
    )
    (net (code "54") (name "PC2") (class "Default")
      (node (ref "R21") (pin "2") (pinfunction "2_2") (pintype "passive"))
      (node (ref "U1") (pin "21") (pinfunction "(TCK)PC2_21") (pintype "bidirectional"))
    )
    (net (code "55") (name "PC3") (class "Default")
      (node (ref "JP12") (pin "1") (pinfunction "1_1") (pintype "passive"))
      (node (ref "U1") (pin "22") (pinfunction "(TMS)PC3_22") (pintype "bidirectional"))
    )
    (net (code "56") (name "PC4") (class "Default")
      (node (ref "JP11") (pin "1") (pinfunction "1_1") (pintype "passive"))
      (node (ref "U1") (pin "23") (pinfunction "(TDO)PC4_23") (pintype "bidirectional"))
    )
    (net (code "57") (name "PC5") (class "Default")
      (node (ref "JP10") (pin "1") (pinfunction "1_1") (pintype "passive"))
      (node (ref "U1") (pin "24") (pinfunction "(TDI)PC5_24") (pintype "bidirectional"))
    )
    (net (code "58") (name "PC6") (class "Default")
      (node (ref "U1") (pin "25") (pinfunction "(TOSC1)PC6_25") (pintype "bidirectional"))
      (node (ref "U7") (pin "1") (pinfunction "1_1") (pintype "output"))
    )
    (net (code "59") (name "PD7") (class "Default")
      (node (ref "R20") (pin "1") (pinfunction "1_1") (pintype "passive"))
      (node (ref "U1") (pin "16") (pinfunction "(OC2)PD7_16") (pintype "bidirectional"))
    )
    (net (code "60") (name "RESET") (class "Default")
      (node (ref "R11") (pin "1") (pinfunction "1_1") (pintype "passive"))
      (node (ref "S1") (pin "1") (pinfunction "1_1") (pintype "passive"))
      (node (ref "S1") (pin "2") (pinfunction "2_2") (pintype "passive"))
      (node (ref "U1") (pin "4") (pinfunction "RESET_4") (pintype "input"))
      (node (ref "X1") (pin "5") (pinfunction "5_5") (pintype "passive"))
    )
    (net (code "61") (name "RX-µC") (class "Default")
      (node (ref "U1") (pin "9") (pinfunction "(RXD)PD0_9") (pintype "bidirectional"))
      (node (ref "U6") (pin "1") (pinfunction "TXD_1") (pintype "output"))
    )
    (net (code "62") (name "SCK_SEG_E") (class "Default")
      (node (ref "U1") (pin "3") (pinfunction "(SCK)PB7_3") (pintype "bidirectional"))
      (node (ref "U2") (pin "1") (pinfunction "A_1") (pintype "input"))
      (node (ref "X1") (pin "3") (pinfunction "3_3") (pintype "passive"))
    )
    (net (code "63") (name "SCL") (class "Default")
      (node (ref "JP19") (pin "1") (pinfunction "1_1") (pintype "passive"))
      (node (ref "M1") (pin "SCL") (pinfunction "P$3_SCL") (pintype "bidirectional"))
      (node (ref "R19") (pin "1") (pinfunction "1_1") (pintype "passive"))
      (node (ref "U1") (pin "19") (pinfunction "PC0(SCL)_19") (pintype "bidirectional"))
      (node (ref "U9") (pin "2") (pinfunction "SCL_2") (pintype "input"))
    )
    (net (code "64") (name "SDA") (class "Default")
      (node (ref "JP18") (pin "1") (pinfunction "1_1") (pintype "passive"))
      (node (ref "M1") (pin "SDA") (pinfunction "P$5_SDA") (pintype "bidirectional"))
      (node (ref "R10") (pin "1") (pinfunction "1_1") (pintype "passive"))
      (node (ref "U1") (pin "20") (pinfunction "PC1(SDA)_20") (pintype "bidirectional"))
      (node (ref "U9") (pin "1") (pinfunction "SDA_1") (pintype "bidirectional"))
    )
    (net (code "65") (name "SEG_A") (class "Default")
      (node (ref "U1") (pin "42") (pinfunction "(AIN0/INT2)PB2_42") (pintype "bidirectional"))
      (node (ref "U3") (pin "3") (pinfunction "A_3") (pintype "input"))
    )
    (net (code "66") (name "SEG_B") (class "Default")
      (node (ref "U1") (pin "43") (pinfunction "(AIN1/OC0)PB3_43") (pintype "bidirectional"))
      (node (ref "U3") (pin "1") (pinfunction "A_1") (pintype "input"))
    )
    (net (code "67") (name "SEG_DP") (class "Default")
      (node (ref "U1") (pin "44") (pinfunction "(SS)PB4_44") (pintype "bidirectional"))
      (node (ref "U2") (pin "9") (pinfunction "A_9") (pintype "input"))
    )
    (net (code "68") (name "SEG_F") (class "Default")
      (node (ref "U1") (pin "41") (pinfunction "(T1)PB1_41") (pintype "bidirectional"))
      (node (ref "U3") (pin "5") (pinfunction "A_5") (pintype "input"))
    )
    (net (code "69") (name "SEG_G") (class "Default")
      (node (ref "U1") (pin "40") (pinfunction "(T0/XCK)PB0_40") (pintype "bidirectional"))
      (node (ref "U3") (pin "9") (pinfunction "A_9") (pintype "input"))
    )
    (net (code "70") (name "STD1") (class "Default")
      (node (ref "R14") (pin "2") (pinfunction "2_2") (pintype "passive"))
      (node (ref "U1") (pin "13") (pinfunction "(OC1B)PD4_13") (pintype "bidirectional"))
      (node (ref "U4") (pin "5") (pinfunction "A_5") (pintype "input"))
    )
    (net (code "71") (name "STD10") (class "Default")
      (node (ref "R13") (pin "2") (pinfunction "2_2") (pintype "passive"))
      (node (ref "U1") (pin "12") (pinfunction "(INT1)PD3_12") (pintype "bidirectional"))
      (node (ref "U4") (pin "9") (pinfunction "A_9") (pintype "input"))
    )
    (net (code "72") (name "TX-µC") (class "Default")
      (node (ref "U1") (pin "10") (pinfunction "(TXD)PD1_10") (pintype "bidirectional"))
      (node (ref "U6") (pin "5") (pinfunction "RXD_5") (pintype "input"))
    )
    (net (code "73") (name "USBM") (class "Default")
      (node (ref "C17") (pin "2") (pinfunction "2_2") (pintype "passive"))
      (node (ref "U6") (pin "16") (pinfunction "USBDM_16") (pintype "bidirectional"))
      (node (ref "X3") (pin "D-") (pinfunction "D-_D-") (pintype "bidirectional"))
    )
    (net (code "74") (name "USBP") (class "Default")
      (node (ref "C16") (pin "2") (pinfunction "2_2") (pintype "passive"))
      (node (ref "U6") (pin "15") (pinfunction "USBDP_15") (pintype "bidirectional"))
      (node (ref "X3") (pin "D+") (pinfunction "D+_D+") (pintype "bidirectional"))
    )
    (net (code "75") (name "unconnected-(M1-P$2-PadSQW)") (class "Default")
      (node (ref "M1") (pin "SQW") (pinfunction "P$2_SQW") (pintype "bidirectional"))
    )
    (net (code "76") (name "unconnected-(M1-P$4-PadSCL2)") (class "Default")
      (node (ref "M1") (pin "SCL2") (pinfunction "P$4_SCL2") (pintype "bidirectional"))
    )
    (net (code "77") (name "unconnected-(M1-P$6-PadSDA2)") (class "Default")
      (node (ref "M1") (pin "SDA2") (pinfunction "P$6_SDA2") (pintype "bidirectional"))
    )
    (net (code "78") (name "unconnected-(U6-CBUS0-Pad23)") (class "Default")
      (node (ref "U6") (pin "23") (pinfunction "CBUS0_23") (pintype "bidirectional"))
    )
    (net (code "79") (name "unconnected-(U6-CBUS1-Pad22)") (class "Default")
      (node (ref "U6") (pin "22") (pinfunction "CBUS1_22") (pintype "bidirectional"))
    )
    (net (code "80") (name "unconnected-(U6-CBUS2-Pad13)") (class "Default")
      (node (ref "U6") (pin "13") (pinfunction "CBUS2_13") (pintype "bidirectional"))
    )
    (net (code "81") (name "unconnected-(U6-CBUS3-Pad14)") (class "Default")
      (node (ref "U6") (pin "14") (pinfunction "CBUS3_14") (pintype "bidirectional"))
    )
    (net (code "82") (name "unconnected-(U6-CBUS4-Pad12)") (class "Default")
      (node (ref "U6") (pin "12") (pinfunction "CBUS4_12") (pintype "bidirectional"))
    )
    (net (code "83") (name "unconnected-(U6-OSCI-Pad27)") (class "Default")
      (node (ref "U6") (pin "27") (pinfunction "OSCI_27") (pintype "input"))
    )
    (net (code "84") (name "unconnected-(U6-OSCO-Pad28)") (class "Default")
      (node (ref "U6") (pin "28") (pinfunction "OSCO_28") (pintype "output"))
    )
    (net (code "85") (name "unconnected-(U6-~{CTS}-Pad11)") (class "Default")
      (node (ref "U6") (pin "11") (pinfunction "~{CTS}_11") (pintype "input"))
    )
    (net (code "86") (name "unconnected-(U6-~{DCD}-Pad10)") (class "Default")
      (node (ref "U6") (pin "10") (pinfunction "~{DCD}_10") (pintype "input"))
    )
    (net (code "87") (name "unconnected-(U6-~{DSR}-Pad9)") (class "Default")
      (node (ref "U6") (pin "9") (pinfunction "~{DSR}_9") (pintype "input"))
    )
    (net (code "88") (name "unconnected-(U6-~{DTR}-Pad2)") (class "Default")
      (node (ref "U6") (pin "2") (pinfunction "~{DTR}_2") (pintype "output"))
    )
    (net (code "89") (name "unconnected-(U6-~{RESET}-Pad19)") (class "Default")
      (node (ref "U6") (pin "19") (pinfunction "~{RESET}_19") (pintype "input"))
    )
    (net (code "90") (name "unconnected-(U6-~{RI}-Pad6)") (class "Default")
      (node (ref "U6") (pin "6") (pinfunction "~{RI}_6") (pintype "input"))
    )
    (net (code "91") (name "unconnected-(U6-~{RTS}-Pad3)") (class "Default")
      (node (ref "U6") (pin "3") (pinfunction "~{RTS}_3") (pintype "output"))
    )
    (net (code "92") (name "unconnected-(U9-OS-Pad3)") (class "Default")
      (node (ref "U9") (pin "3") (pinfunction "OS_3") (pintype "output"))
    )
  )
)
